# IR_Schreib_Lesekopf_RS232_Neu.net
KiCad netlist of a schematic drawn in EAGLE
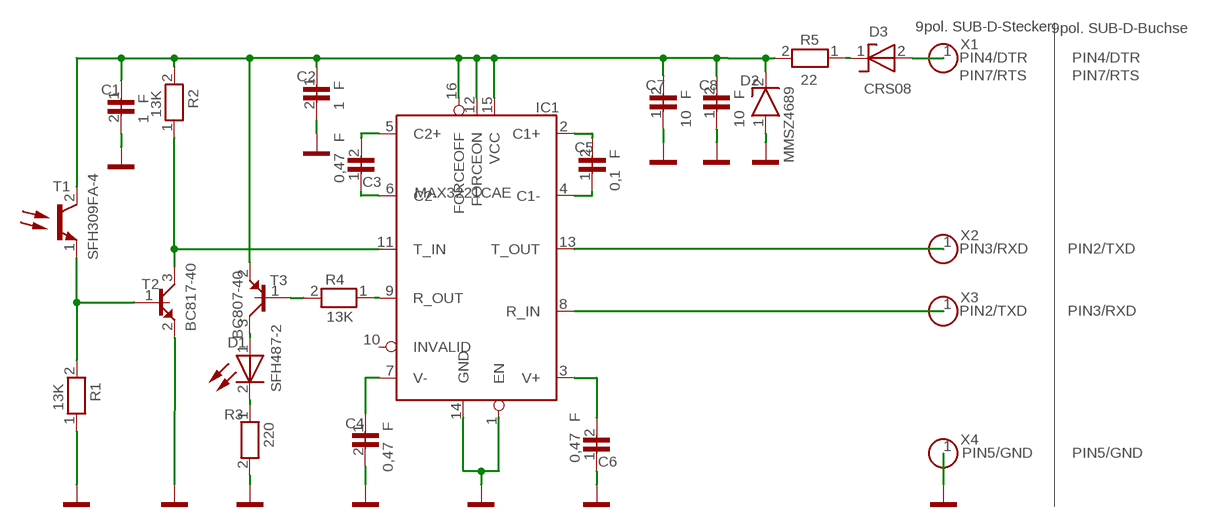
[diagram p0: schematic, sheet 1]

(export (version "E")
  (design (tool "Eeschema 10.0.6"))
  (components
    (comp (ref "C1")
      (value "1�F")
      (footprint "eagle-import:0603_KLEIN")
      (libsource (lib "eagle-import") (part "1�F"))
    )
    (comp (ref "C2")
      (value "1�F")
      (footprint "eagle-import:0603_KLEIN")
      (libsource (lib "eagle-import") (part "1�F"))
    )
    (comp (ref "C3")
      (value "0,47�F")
      (footprint "eagle-import:0603")
      (libsource (lib "eagle-import") (part "0,47�F"))
    )
    (comp (ref "C4")
      (value "0,47�F")
      (footprint "eagle-import:0603")
      (libsource (lib "eagle-import") (part "0,47�F"))
    )
    (comp (ref "C5")
      (value "0,1�F")
      (footprint "eagle-import:0603")
      (libsource (lib "eagle-import") (part "0,1�F"))
    )
    (comp (ref "C6")
      (value "0,47�F")
      (footprint "eagle-import:0603")
      (libsource (lib "eagle-import") (part "0,47�F"))
    )
    (comp (ref "C7")
      (value "10�F")
      (footprint "eagle-import:0805_KLEIN")
      (libsource (lib "eagle-import") (part "10�F"))
    )
    (comp (ref "C8")
      (value "10�F")
      (footprint "eagle-import:0805_KLEIN")
      (libsource (lib "eagle-import") (part "10�F"))
    )
    (comp (ref "D1")
      (value "SFH487-2")
      (footprint "eagle-import:LED_3MM")
      (libsource (lib "eagle-import") (part "SFH487-2"))
    )
    (comp (ref "D2")
      (value "MMSZ4689")
      (footprint "eagle-import:SOD123")
      (libsource (lib "eagle-import") (part "MMSZ4689"))
    )
    (comp (ref "D3")
      (value "CRS08")
      (footprint "eagle-import:SOD123")
      (libsource (lib "eagle-import") (part "CRS08"))
    )
    (comp (ref "IC1")
      (value "MAX3221CAE")
      (footprint "eagle-import:SSOP16")
      (libsource (lib "eagle-import") (part "MAX3221CAE"))
    )
    (comp (ref "R1")
      (value "13K")
      (footprint "eagle-import:0603_KLEIN")
      (libsource (lib "eagle-import") (part "13K"))
    )
    (comp (ref "R2")
      (value "13K")
      (footprint "eagle-import:0603_KLEIN")
      (libsource (lib "eagle-import") (part "13K"))
    )
    (comp (ref "R3")
      (value "220")
      (footprint "eagle-import:0603_KLEIN")
      (libsource (lib "eagle-import") (part "220"))
    )
    (comp (ref "R4")
      (value "13K")
      (footprint "eagle-import:0603_KLEIN")
      (libsource (lib "eagle-import") (part "13K"))
    )
    (comp (ref "R5")
      (value "22")
      (footprint "eagle-import:1206")
      (libsource (lib "eagle-import") (part "22"))
    )
    (comp (ref "T1")
      (value "SFH309FA-4")
      (footprint "eagle-import:LED_3MM")
      (libsource (lib "eagle-import") (part "SFH309FA-4"))
    )
    (comp (ref "T2")
      (value "BC817-40")
      (footprint "eagle-import:SOT23_3")
      (libsource (lib "eagle-import") (part "BC817-40"))
    )
    (comp (ref "T3")
      (value "BC807-40")
      (footprint "eagle-import:SOT23_3")
      (libsource (lib "eagle-import") (part "BC807-40"))
    )
    (comp (ref "X1")
      (value "PIN4/DTR")
      (footprint "eagle-import:LOETPUNKT")
      (libsource (lib "eagle-import") (part "PIN4/DTR"))
    )
    (comp (ref "X2")
      (value "PIN3/RXD")
      (footprint "eagle-import:LOETPUNKT")
      (libsource (lib "eagle-import") (part "PIN3/RXD"))
    )
    (comp (ref "X3")
      (value "PIN2/TXD")
      (footprint "eagle-import:LOETPUNKT")
      (libsource (lib "eagle-import") (part "PIN2/TXD"))
    )
    (comp (ref "X4")
      (value "PIN5/GND")
      (footprint "eagle-import:LOETPUNKT")
      (libsource (lib "eagle-import") (part "PIN5/GND"))
    )
  )
  (nets
    (net (code "1") (name "GND") (class "Default")
      (node (ref "C1") (pin "2") (pinfunction "2_2") (pintype "passive"))
      (node (ref "C2") (pin "2") (pinfunction "2_2") (pintype "passive"))
      (node (ref "C4") (pin "2") (pinfunction "2_2") (pintype "passive"))
      (node (ref "C6") (pin "1") (pinfunction "1_1") (pintype "passive"))
      (node (ref "C7") (pin "1") (pinfunction "1_1") (pintype "passive"))
      (node (ref "C8") (pin "1") (pinfunction "1_1") (pintype "passive"))
      (node (ref "D2") (pin "1") (pinfunction "1_1") (pintype "passive"))
      (node (ref "IC1") (pin "1") (pinfunction "EN_1") (pintype "input"))
      (node (ref "IC1") (pin "14") (pinfunction "GND_14") (pintype "power_in"))
      (node (ref "R1") (pin "1") (pinfunction "1_1") (pintype "passive"))
      (node (ref "R3") (pin "2") (pinfunction "2_2") (pintype "passive"))
      (node (ref "T2") (pin "2") (pinfunction "2_2") (pintype "passive"))
      (node (ref "X4") (pin "1") (pinfunction "1_1") (pintype "passive"))
    )
    (net (code "2") (name "Net-(D1-Pad1)") (class "Default")
      (node (ref "D1") (pin "1") (pinfunction "1_1") (pintype "passive"))
      (node (ref "T3") (pin "3") (pinfunction "3_3") (pintype "passive"))
    )
    (net (code "3") (name "Net-(D1-Pad2)") (class "Default")
      (node (ref "D1") (pin "2") (pinfunction "2_2") (pintype "passive"))
      (node (ref "R3") (pin "1") (pinfunction "1_1") (pintype "passive"))
    )
    (net (code "4") (name "Net-(D3-Pad1)") (class "Default")
      (node (ref "D3") (pin "1") (pinfunction "1_1") (pintype "passive"))
      (node (ref "R5") (pin "1") (pinfunction "1_1") (pintype "passive"))
    )
    (net (code "5") (name "Net-(D3-Pad2)") (class "Default")
      (node (ref "D3") (pin "2") (pinfunction "2_2") (pintype "passive"))
      (node (ref "X1") (pin "1") (pinfunction "1_1") (pintype "passive"))
    )
    (net (code "6") (name "Net-(IC1-C1+)") (class "Default")
      (node (ref "C5") (pin "2") (pinfunction "2_2") (pintype "passive"))
      (node (ref "IC1") (pin "2") (pinfunction "C1+_2") (pintype "passive"))
    )
    (net (code "7") (name "Net-(IC1-C1-)") (class "Default")
      (node (ref "C5") (pin "1") (pinfunction "1_1") (pintype "passive"))
      (node (ref "IC1") (pin "4") (pinfunction "C1-_4") (pintype "passive"))
    )
    (net (code "8") (name "Net-(IC1-C2+)") (class "Default")
      (node (ref "C3") (pin "2") (pinfunction "2_2") (pintype "passive"))
      (node (ref "IC1") (pin "5") (pinfunction "C2+_5") (pintype "passive"))
    )
    (net (code "9") (name "Net-(IC1-C2-)") (class "Default")
      (node (ref "C3") (pin "1") (pinfunction "1_1") (pintype "passive"))
      (node (ref "IC1") (pin "6") (pinfunction "C2-_6") (pintype "passive"))
    )
    (net (code "10") (name "Net-(IC1-FORCEOFF)") (class "Default")
      (node (ref "C1") (pin "1") (pinfunction "1_1") (pintype "passive"))
      (node (ref "C2") (pin "1") (pinfunction "1_1") (pintype "passive"))
      (node (ref "C7") (pin "2") (pinfunction "2_2") (pintype "passive"))
      (node (ref "C8") (pin "2") (pinfunction "2_2") (pintype "passive"))
      (node (ref "D2") (pin "2") (pinfunction "2_2") (pintype "passive"))
      (node (ref "IC1") (pin "12") (pinfunction "FORCEON_12") (pintype "passive"))
      (node (ref "IC1") (pin "15") (pinfunction "VCC_15") (pintype "power_in"))
      (node (ref "IC1") (pin "16") (pinfunction "FORCEOFF_16") (pintype "passive"))
      (node (ref "R2") (pin "2") (pinfunction "2_2") (pintype "passive"))
      (node (ref "R5") (pin "2") (pinfunction "2_2") (pintype "passive"))
      (node (ref "T1") (pin "2") (pinfunction "2_2") (pintype "passive"))
      (node (ref "T3") (pin "2") (pinfunction "2_2") (pintype "passive"))
    )
    (net (code "11") (name "Net-(IC1-R_IN)") (class "Default")
      (node (ref "IC1") (pin "8") (pinfunction "R_IN_8") (pintype "input"))
      (node (ref "X3") (pin "1") (pinfunction "1_1") (pintype "passive"))
    )
    (net (code "12") (name "Net-(IC1-R_OUT)") (class "Default")
      (node (ref "IC1") (pin "9") (pinfunction "R_OUT_9") (pintype "output"))
      (node (ref "R4") (pin "1") (pinfunction "1_1") (pintype "passive"))
    )
    (net (code "13") (name "Net-(IC1-T_IN)") (class "Default")
      (node (ref "IC1") (pin "11") (pinfunction "T_IN_11") (pintype "input"))
      (node (ref "R2") (pin "1") (pinfunction "1_1") (pintype "passive"))
      (node (ref "T2") (pin "3") (pinfunction "3_3") (pintype "passive"))
    )
    (net (code "14") (name "Net-(IC1-T_OUT)") (class "Default")
      (node (ref "IC1") (pin "13") (pinfunction "T_OUT_13") (pintype "output"))
      (node (ref "X2") (pin "1") (pinfunction "1_1") (pintype "passive"))
    )
    (net (code "15") (name "Net-(IC1-V+)") (class "Default")
      (node (ref "C6") (pin "2") (pinfunction "2_2") (pintype "passive"))
      (node (ref "IC1") (pin "3") (pinfunction "V+_3") (pintype "power_in"))
    )
    (net (code "16") (name "Net-(IC1-V-)") (class "Default")
      (node (ref "C4") (pin "1") (pinfunction "1_1") (pintype "passive"))
      (node (ref "IC1") (pin "7") (pinfunction "V-_7") (pintype "power_in"))
    )
    (net (code "17") (name "Net-(R1-Pad2)") (class "Default")
      (node (ref "R1") (pin "2") (pinfunction "2_2") (pintype "passive"))
      (node (ref "T1") (pin "1") (pinfunction "1_1") (pintype "passive"))
      (node (ref "T2") (pin "1") (pinfunction "1_1") (pintype "passive"))
    )
    (net (code "18") (name "Net-(R4-Pad2)") (class "Default")
      (node (ref "R4") (pin "2") (pinfunction "2_2") (pintype "passive"))
      (node (ref "T3") (pin "1") (pinfunction "1_1") (pintype "passive"))
    )
    (net (code "19") (name "unconnected-(IC1-INVALID-Pad10)") (class "Default")
      (node (ref "IC1") (pin "10") (pinfunction "INVALID_10") (pintype "output"))
    )
  )
)
